# Color_Detector_RPi_Board.net
KiCad netlist of a schematic drawn in EAGLE
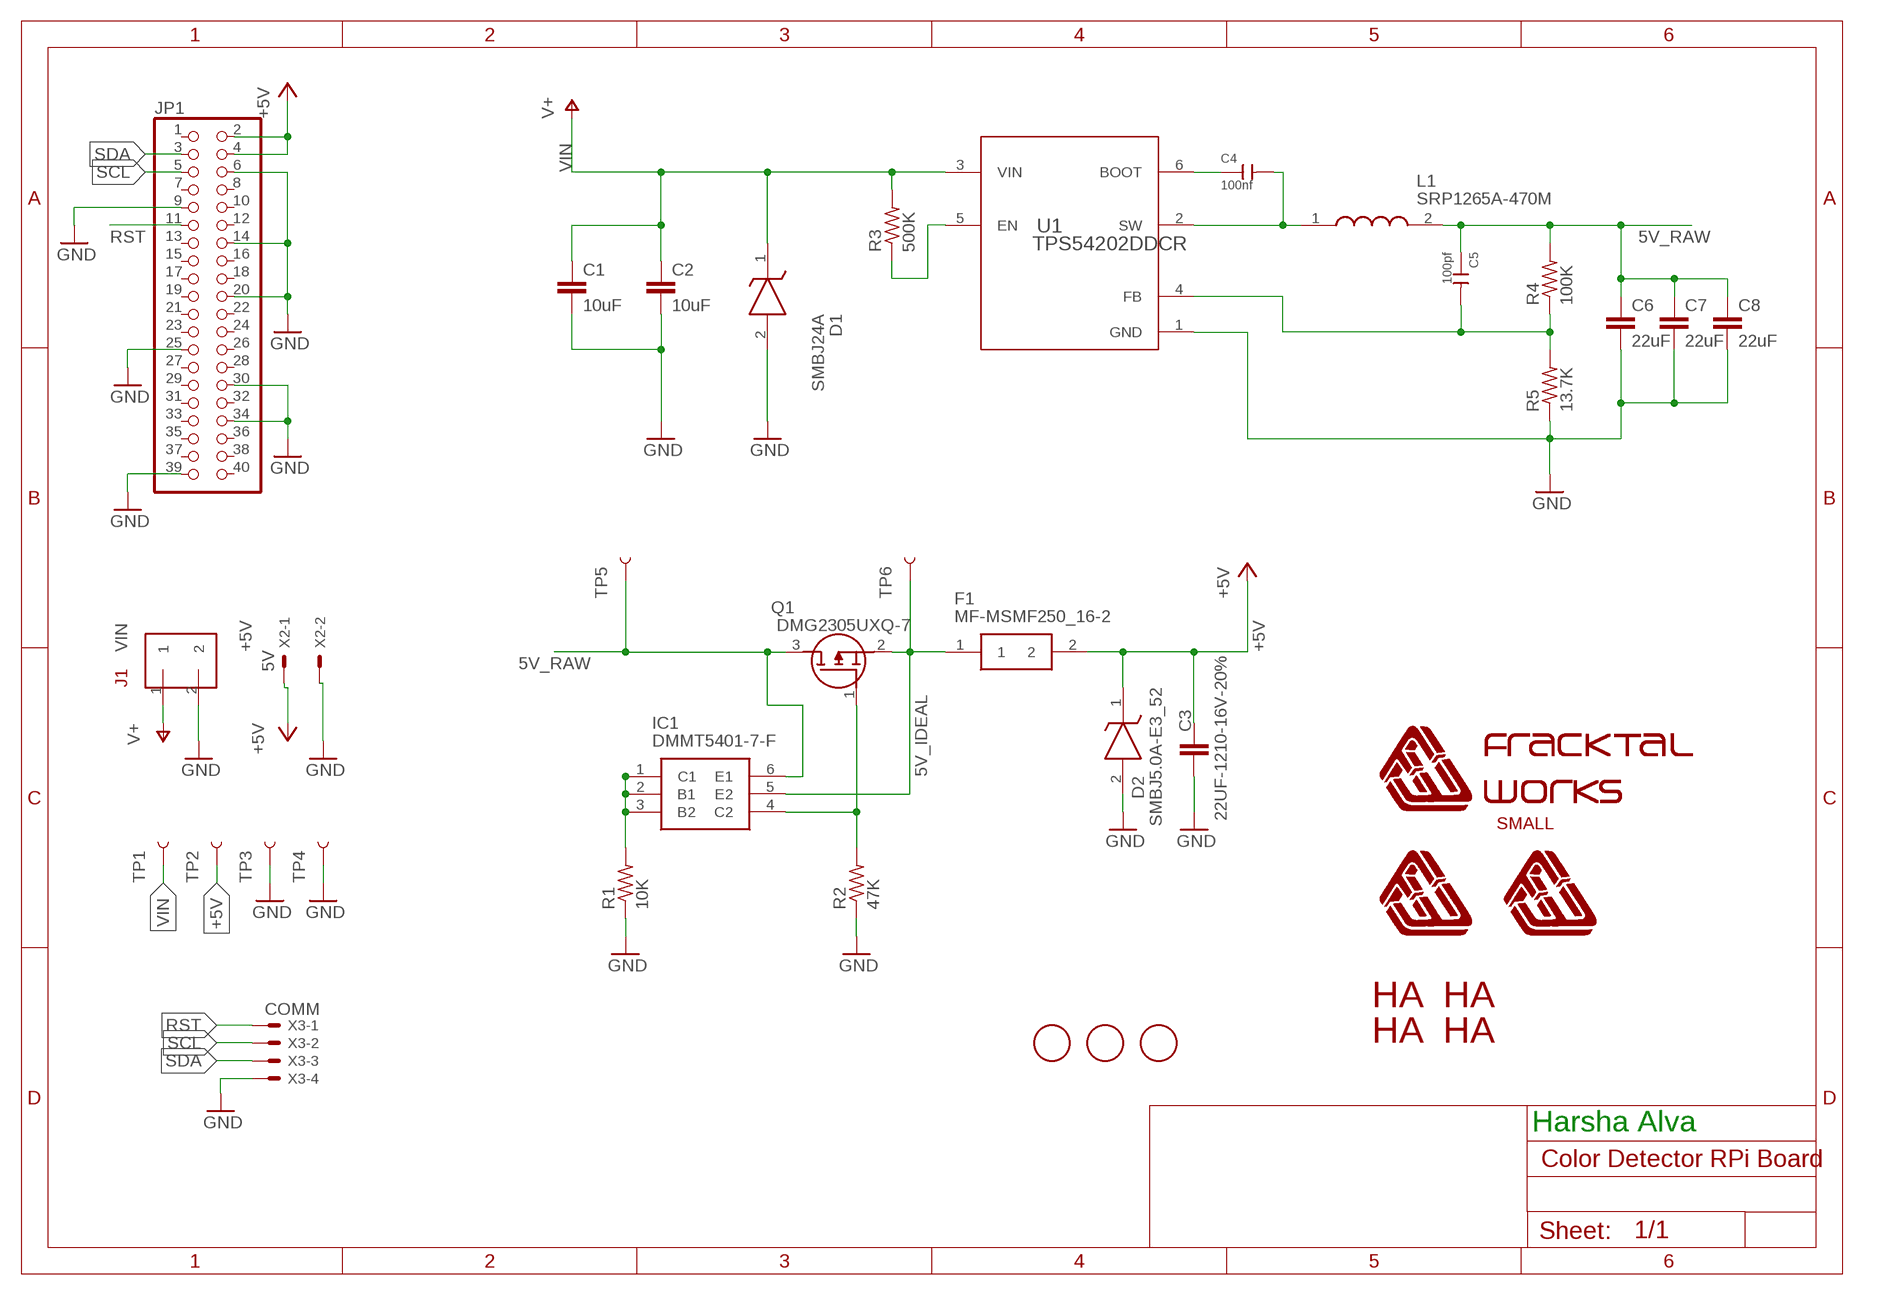
[diagram p0: schematic, sheet 1]

(export (version "E")
  (design (tool "Eeschema 10.0.6"))
  (components
    (comp (ref "$1_39_$_2020-06-29_16-08-13")
      (value "HA_MARK")
      (footprint "eagle-import:HA_MARK")
      (libsource (lib "eagle-import") (part "HA_MARK"))
    )
    (comp (ref "$1_40_$_2020-06-29_16-08-1")
      (value "HA_MARK")
      (footprint "eagle-import:HA_MARK")
      (libsource (lib "eagle-import") (part "HA_MARK"))
    )
    (comp (ref "$1_40_$_2020-06-29_16-08-13")
      (value "HA_MARK")
      (footprint "eagle-import:HA_MARK")
      (libsource (lib "eagle-import") (part "HA_MARK"))
    )
    (comp (ref "C1")
      (value "10uF")
      (footprint "eagle-import:1210")
      (libsource (lib "eagle-import") (part "10UF-1210-50V-20%"))
    )
    (comp (ref "C2")
      (value "10uF")
      (footprint "eagle-import:1210")
      (libsource (lib "eagle-import") (part "10UF-1210-50V-20%"))
    )
    (comp (ref "C3")
      (value "22UF-1210-16V-20%")
      (footprint "eagle-import:1210")
      (libsource (lib "eagle-import") (part "22UF-1210-16V-20%"))
    )
    (comp (ref "C4")
      (value "100nf")
      (footprint "eagle-import:C0603")
      (fields (field (name "MPN") "CC0603KRX7R9BB104"))
      (libsource (lib "eagle-import") (part "CERAMIC-100NF-50V-10%-X7R(0603)"))
    )
    (comp (ref "C5")
      (value "100pf")
      (footprint "eagle-import:C0603")
      (fields (field (name "MPN") "CC0603JRNPO9BN101"))
      (libsource (lib "eagle-import") (part "CERAMIC-100PF-50V-5%-NPO(0603)"))
    )
    (comp (ref "C6")
      (value "22uF")
      (footprint "eagle-import:1210")
      (libsource (lib "eagle-import") (part "22UF-1210-16V-20%"))
    )
    (comp (ref "C7")
      (value "22uF")
      (footprint "eagle-import:1210")
      (libsource (lib "eagle-import") (part "22UF-1210-16V-20%"))
    )
    (comp (ref "C8")
      (value "22uF")
      (footprint "eagle-import:1210")
      (libsource (lib "eagle-import") (part "22UF-1210-16V-20%"))
    )
    (comp (ref "D1")
      (value "SMBJ24A")
      (footprint "eagle-import:DIOM5436X244N")
      (fields (field (name "MOUSER_PART_NUMBER") "652-SMBJ24A"))
      (libsource (lib "eagle-import") (part "SMBJ24A"))
    )
    (comp (ref "D2")
      (value "SMBJ5.0A-E3_52")
      (footprint "eagle-import:DIOM5436X244N")
      (fields
        (field (name "MANUFACTURER_PART_NUMBER") "SMBJ5.0A-E3/52")
        (field (name "MOUSER_PART_NUMBER") "625-SMBJ5.0A-E3")
        (field (name "RS_PART_NUMBER") "1652507")
      )
      (libsource (lib "eagle-import") (part "SMBJ5.0A-E3_52"))
    )
    (comp (ref "F1")
      (value "MF-MSMF250_16-2")
      (footprint "eagle-import:FUSC4632X160N")
      (fields
        (field (name "MANUFACTURER_PART_NUMBER") "MF-MSMF250/16-2")
        (field (name "MOUSER_PART_NUMBER") "652-MF-MSMF250/16-2")
        (field (name "RS_PART_NUMBER") "6478229P")
      )
      (libsource (lib "eagle-import") (part "MF-MSMF250_16-2"))
    )
    (comp (ref "FWLOGO_1")
      (value "FWLOGO")
      (footprint "eagle-import:FWLOGO")
      (libsource (lib "eagle-import") (part "FWLOGO"))
    )
    (comp (ref "FWLOGO_2")
      (value "FWLOGO")
      (footprint "eagle-import:FWLOGO")
      (libsource (lib "eagle-import") (part "FWLOGO"))
    )
    (comp (ref "FW_TXT_S_2")
      (value "FWLOGO_TEXT_SMALL")
      (footprint "eagle-import:FWLOGO_TEXT_SMALL")
      (libsource (lib "eagle-import") (part "FWLOGO_TEXT_SMALL"))
    )
    (comp (ref "IC1")
      (value "DMMT5401-7-F")
      (footprint "eagle-import:SOT95P275X110-6N")
      (fields (field (name "MOUSER_PART_NUMBER") "621-DMMT5401-7-F"))
      (libsource (lib "eagle-import") (part "DMMT5401-7-F"))
    )
    (comp (ref "J1")
      (value "TERMINALBLOCK/TOYO/2PIN/5MMPITCH")
      (footprint "eagle-import:TERMINALBLOCK_TOYO_2PIN_5MMPITCH")
      (libsource (lib "eagle-import") (part "TERMINALBLOCK/TOYO/2PIN/5MMPITCH"))
    )
    (comp (ref "JP1")
      (value "RASPBERRYPI_3B_GPIO")
      (footprint "eagle-import:RASPBERRYPI_3B_GPIO")
      (libsource (lib "eagle-import") (part "RASPBERRYPI_3B_GPIO"))
    )
    (comp (ref "L1")
      (value "SRP1265A-470M")
      (footprint "eagle-import:SRP1265A")
      (fields
        (field (name "MOUSER_PART_NUMBER") "652-SRP1265A-470M")
        (field (name "RS_PART_NUMBER") "8193513P")
      )
      (libsource (lib "eagle-import") (part "SRP1265A-470M"))
    )
    (comp (ref "M_HA_1")
      (value "HA_MARK")
      (footprint "eagle-import:HA_MARK")
      (libsource (lib "eagle-import") (part "HA_MARK"))
    )
    (comp (ref "Q1")
      (value "DMG2305UXQ-7")
      (footprint "eagle-import:SOT96P240X110-3N")
      (fields (field (name "MOUSER_PART_NUMBER") "621-DMG2305UXQ-7"))
      (libsource (lib "eagle-import") (part "DMG2305UXQ-7"))
    )
    (comp (ref "R1")
      (value "10K")
      (footprint "eagle-import:M0805")
      (libsource (lib "eagle-import") (part "resistor_348_R-US_M0805"))
    )
    (comp (ref "R2")
      (value "47K")
      (footprint "eagle-import:M0805")
      (libsource (lib "eagle-import") (part "resistor_348_R-US_M0805"))
    )
    (comp (ref "R3")
      (value "500K")
      (footprint "eagle-import:R0603")
      (libsource (lib "eagle-import") (part "R-US_R0603"))
    )
    (comp (ref "R4")
      (value "100K")
      (footprint "eagle-import:R0603")
      (libsource (lib "eagle-import") (part "R-US_R0603"))
    )
    (comp (ref "R5")
      (value "13.7K")
      (footprint "eagle-import:R0603")
      (libsource (lib "eagle-import") (part "R-US_R0603"))
    )
    (comp (ref "TP1")
      (value "TEST-POINT3X5")
      (footprint "eagle-import:PAD.03X.05")
      (libsource (lib "eagle-import") (part "TEST-POINT3X5"))
    )
    (comp (ref "TP2")
      (value "TEST-POINT3X5")
      (footprint "eagle-import:PAD.03X.05")
      (libsource (lib "eagle-import") (part "TEST-POINT3X5"))
    )
    (comp (ref "TP3")
      (value "TEST-POINT3X5")
      (footprint "eagle-import:PAD.03X.05")
      (libsource (lib "eagle-import") (part "TEST-POINT3X5"))
    )
    (comp (ref "TP4")
      (value "TEST-POINT3X5")
      (footprint "eagle-import:PAD.03X.05")
      (libsource (lib "eagle-import") (part "TEST-POINT3X5"))
    )
    (comp (ref "TP5")
      (value "TEST-POINT3X5")
      (footprint "eagle-import:PAD.03X.05")
      (libsource (lib "eagle-import") (part "TEST-POINT3X5"))
    )
    (comp (ref "TP6")
      (value "TEST-POINT3X5")
      (footprint "eagle-import:PAD.03X.05")
      (libsource (lib "eagle-import") (part "TEST-POINT3X5"))
    )
    (comp (ref "U$1")
      (value "FIDUCIAL")
      (footprint "eagle-import:FIDUCIAL_1MM")
      (libsource (lib "eagle-import") (part "FIDUCIAL"))
    )
    (comp (ref "U$2")
      (value "FIDUCIAL")
      (footprint "eagle-import:FIDUCIAL_1MM")
      (libsource (lib "eagle-import") (part "FIDUCIAL"))
    )
    (comp (ref "U$3")
      (value "FIDUCIAL")
      (footprint "eagle-import:FIDUCIAL_1MM")
      (libsource (lib "eagle-import") (part "FIDUCIAL"))
    )
    (comp (ref "U1")
      (value "TPS54202DDCR")
      (footprint "eagle-import:DDC0006A_N")
      (fields
        (field (name "ALTERNATEPARTNUMBER") "TPS54202DDCT")
        (field (name "MANUFACTURER") "Texas Instruments")
      )
      (libsource (lib "eagle-import") (part "TPS54202DDCR"))
    )
    (comp (ref "X2")
      (value "5V")
      (footprint "eagle-import:JST-XH-02-PACKAGE-LONG-PAD")
      (libsource (lib "eagle-import") (part "JST-XH-02-PIN-LONG-PAD"))
    )
    (comp (ref "X3")
      (value "COMM")
      (footprint "eagle-import:JST-XH-04-PACKAGE-ROUND-PAD")
      (libsource (lib "eagle-import") (part "JST-XH-04-PIN-ROUND-PAD"))
    )
  )
  (nets
    (net (code "1") (name "+5V") (class "Default")
      (node (ref "C3") (pin "2") (pinfunction "2_2") (pintype "passive"))
      (node (ref "D2") (pin "1") (pinfunction "K_1") (pintype "bidirectional"))
      (node (ref "F1") (pin "2") (pinfunction "2_2") (pintype "bidirectional"))
      (node (ref "JP1") (pin "2") (pinfunction "2_2") (pintype "passive"))
      (node (ref "JP1") (pin "4") (pinfunction "4_4") (pintype "passive"))
      (node (ref "TP2") (pin "P$1") (pinfunction "1_P$1") (pintype "bidirectional"))
      (node (ref "X2") (pin "1") (pinfunction "S_1") (pintype "passive"))
    )
    (net (code "2") (name "/5V_IDEAL") (class "Default")
      (node (ref "F1") (pin "1") (pinfunction "1_1") (pintype "bidirectional"))
      (node (ref "IC1") (pin "5") (pinfunction "E2_5") (pintype "bidirectional"))
      (node (ref "Q1") (pin "2") (pinfunction "S_2") (pintype "bidirectional"))
      (node (ref "TP6") (pin "P$1") (pinfunction "1_P$1") (pintype "bidirectional"))
    )
    (net (code "3") (name "/5V_RAW") (class "Default")
      (node (ref "C5") (pin "1") (pinfunction "1_1") (pintype "passive"))
      (node (ref "C6") (pin "1") (pinfunction "1_1") (pintype "passive"))
      (node (ref "C7") (pin "1") (pinfunction "1_1") (pintype "passive"))
      (node (ref "C8") (pin "1") (pinfunction "1_1") (pintype "passive"))
      (node (ref "IC1") (pin "6") (pinfunction "E1_6") (pintype "bidirectional"))
      (node (ref "L1") (pin "2") (pinfunction "2_2") (pintype "bidirectional"))
      (node (ref "Q1") (pin "3") (pinfunction "D_3") (pintype "bidirectional"))
      (node (ref "R4") (pin "2") (pinfunction "2_2") (pintype "passive"))
      (node (ref "TP5") (pin "P$1") (pinfunction "1_P$1") (pintype "bidirectional"))
    )
    (net (code "4") (name "GND") (class "Default")
      (node (ref "C1") (pin "2") (pinfunction "2_2") (pintype "passive"))
      (node (ref "C2") (pin "2") (pinfunction "2_2") (pintype "passive"))
      (node (ref "C3") (pin "1") (pinfunction "1_1") (pintype "passive"))
      (node (ref "C6") (pin "2") (pinfunction "2_2") (pintype "passive"))
      (node (ref "C7") (pin "2") (pinfunction "2_2") (pintype "passive"))
      (node (ref "C8") (pin "2") (pinfunction "2_2") (pintype "passive"))
      (node (ref "D1") (pin "2") (pinfunction "A_2") (pintype "bidirectional"))
      (node (ref "D2") (pin "2") (pinfunction "A_2") (pintype "bidirectional"))
      (node (ref "J1") (pin "2") (pinfunction "2_2") (pintype "bidirectional"))
      (node (ref "JP1") (pin "14") (pinfunction "14_14") (pintype "passive"))
      (node (ref "JP1") (pin "20") (pinfunction "20_20") (pintype "passive"))
      (node (ref "JP1") (pin "25") (pinfunction "25_25") (pintype "passive"))
      (node (ref "JP1") (pin "30") (pinfunction "30_30") (pintype "passive"))
      (node (ref "JP1") (pin "34") (pinfunction "34_34") (pintype "passive"))
      (node (ref "JP1") (pin "39") (pinfunction "39_39") (pintype "passive"))
      (node (ref "JP1") (pin "6") (pinfunction "6_6") (pintype "passive"))
      (node (ref "JP1") (pin "9") (pinfunction "9_9") (pintype "passive"))
      (node (ref "R1") (pin "1") (pinfunction "1_1") (pintype "passive"))
      (node (ref "R2") (pin "1") (pinfunction "1_1") (pintype "passive"))
      (node (ref "R5") (pin "1") (pinfunction "1_1") (pintype "passive"))
      (node (ref "TP3") (pin "P$1") (pinfunction "1_P$1") (pintype "bidirectional"))
      (node (ref "TP4") (pin "P$1") (pinfunction "1_P$1") (pintype "bidirectional"))
      (node (ref "U1") (pin "1") (pinfunction "GND_1") (pintype "power_in"))
      (node (ref "X2") (pin "2") (pinfunction "S_2") (pintype "passive"))
      (node (ref "X3") (pin "4") (pinfunction "S_4") (pintype "passive"))
    )
    (net (code "5") (name "Net-(IC1-B1)") (class "Default")
      (node (ref "IC1") (pin "1") (pinfunction "C1_1") (pintype "bidirectional"))
      (node (ref "IC1") (pin "2") (pinfunction "B1_2") (pintype "bidirectional"))
      (node (ref "IC1") (pin "3") (pinfunction "B2_3") (pintype "bidirectional"))
      (node (ref "R1") (pin "2") (pinfunction "2_2") (pintype "passive"))
    )
    (net (code "6") (name "Net-(IC1-C2)") (class "Default")
      (node (ref "IC1") (pin "4") (pinfunction "C2_4") (pintype "bidirectional"))
      (node (ref "Q1") (pin "1") (pinfunction "G_1") (pintype "bidirectional"))
      (node (ref "R2") (pin "2") (pinfunction "2_2") (pintype "passive"))
    )
    (net (code "7") (name "Net-(U1-BOOT)") (class "Default")
      (node (ref "C4") (pin "1") (pinfunction "1_1") (pintype "passive"))
      (node (ref "U1") (pin "6") (pinfunction "BOOT_6") (pintype "power_in"))
    )
    (net (code "8") (name "Net-(U1-EN)") (class "Default")
      (node (ref "R3") (pin "1") (pinfunction "1_1") (pintype "passive"))
      (node (ref "U1") (pin "5") (pinfunction "EN_5") (pintype "input"))
    )
    (net (code "9") (name "Net-(U1-FB)") (class "Default")
      (node (ref "C5") (pin "2") (pinfunction "2_2") (pintype "passive"))
      (node (ref "R4") (pin "1") (pinfunction "1_1") (pintype "passive"))
      (node (ref "R5") (pin "2") (pinfunction "2_2") (pintype "passive"))
      (node (ref "U1") (pin "4") (pinfunction "FB_4") (pintype "input"))
    )
    (net (code "10") (name "Net-(U1-SW)") (class "Default")
      (node (ref "C4") (pin "2") (pinfunction "2_2") (pintype "passive"))
      (node (ref "L1") (pin "1") (pinfunction "1_1") (pintype "bidirectional"))
      (node (ref "U1") (pin "2") (pinfunction "SW_2") (pintype "power_in"))
    )
    (net (code "11") (name "RST") (class "Default")
      (node (ref "JP1") (pin "11") (pinfunction "11_11") (pintype "passive"))
      (node (ref "X3") (pin "1") (pinfunction "S_1") (pintype "passive"))
    )
    (net (code "12") (name "SCL") (class "Default")
      (node (ref "JP1") (pin "5") (pinfunction "5_5") (pintype "passive"))
      (node (ref "X3") (pin "2") (pinfunction "S_2") (pintype "passive"))
    )
    (net (code "13") (name "SDA") (class "Default")
      (node (ref "JP1") (pin "3") (pinfunction "3_3") (pintype "passive"))
      (node (ref "X3") (pin "3") (pinfunction "S_3") (pintype "passive"))
    )
    (net (code "14") (name "VIN") (class "Default")
      (node (ref "C1") (pin "1") (pinfunction "1_1") (pintype "passive"))
      (node (ref "C2") (pin "1") (pinfunction "1_1") (pintype "passive"))
      (node (ref "D1") (pin "1") (pinfunction "K_1") (pintype "bidirectional"))
      (node (ref "J1") (pin "1") (pinfunction "1_1") (pintype "bidirectional"))
      (node (ref "R3") (pin "2") (pinfunction "2_2") (pintype "passive"))
      (node (ref "TP1") (pin "P$1") (pinfunction "1_P$1") (pintype "bidirectional"))
      (node (ref "U1") (pin "3") (pinfunction "VIN_3") (pintype "power_in"))
    )
    (net (code "15") (name "unconnected-(JP1-Pad1)") (class "Default")
      (node (ref "JP1") (pin "1") (pinfunction "1_1") (pintype "passive"))
    )
    (net (code "16") (name "unconnected-(JP1-Pad7)") (class "Default")
      (node (ref "JP1") (pin "7") (pinfunction "7_7") (pintype "passive"))
    )
    (net (code "17") (name "unconnected-(JP1-Pad8)") (class "Default")
      (node (ref "JP1") (pin "8") (pinfunction "8_8") (pintype "passive"))
    )
    (net (code "18") (name "unconnected-(JP1-Pad10)") (class "Default")
      (node (ref "JP1") (pin "10") (pinfunction "10_10") (pintype "passive"))
    )
    (net (code "19") (name "unconnected-(JP1-Pad12)") (class "Default")
      (node (ref "JP1") (pin "12") (pinfunction "12_12") (pintype "passive"))
    )
    (net (code "20") (name "unconnected-(JP1-Pad13)") (class "Default")
      (node (ref "JP1") (pin "13") (pinfunction "13_13") (pintype "passive"))
    )
    (net (code "21") (name "unconnected-(JP1-Pad15)") (class "Default")
      (node (ref "JP1") (pin "15") (pinfunction "15_15") (pintype "passive"))
    )
    (net (code "22") (name "unconnected-(JP1-Pad16)") (class "Default")
      (node (ref "JP1") (pin "16") (pinfunction "16_16") (pintype "passive"))
    )
    (net (code "23") (name "unconnected-(JP1-Pad17)") (class "Default")
      (node (ref "JP1") (pin "17") (pinfunction "17_17") (pintype "passive"))
    )
    (net (code "24") (name "unconnected-(JP1-Pad18)") (class "Default")
      (node (ref "JP1") (pin "18") (pinfunction "18_18") (pintype "passive"))
    )
    (net (code "25") (name "unconnected-(JP1-Pad19)") (class "Default")
      (node (ref "JP1") (pin "19") (pinfunction "19_19") (pintype "passive"))
    )
    (net (code "26") (name "unconnected-(JP1-Pad21)") (class "Default")
      (node (ref "JP1") (pin "21") (pinfunction "21_21") (pintype "passive"))
    )
    (net (code "27") (name "unconnected-(JP1-Pad22)") (class "Default")
      (node (ref "JP1") (pin "22") (pinfunction "22_22") (pintype "passive"))
    )
    (net (code "28") (name "unconnected-(JP1-Pad23)") (class "Default")
      (node (ref "JP1") (pin "23") (pinfunction "23_23") (pintype "passive"))
    )
    (net (code "29") (name "unconnected-(JP1-Pad24)") (class "Default")
      (node (ref "JP1") (pin "24") (pinfunction "24_24") (pintype "passive"))
    )
    (net (code "30") (name "unconnected-(JP1-Pad26)") (class "Default")
      (node (ref "JP1") (pin "26") (pinfunction "26_26") (pintype "passive"))
    )
    (net (code "31") (name "unconnected-(JP1-Pad27)") (class "Default")
      (node (ref "JP1") (pin "27") (pinfunction "27_27") (pintype "passive"))
    )
    (net (code "32") (name "unconnected-(JP1-Pad28)") (class "Default")
      (node (ref "JP1") (pin "28") (pinfunction "28_28") (pintype "passive"))
    )
    (net (code "33") (name "unconnected-(JP1-Pad29)") (class "Default")
      (node (ref "JP1") (pin "29") (pinfunction "29_29") (pintype "passive"))
    )
    (net (code "34") (name "unconnected-(JP1-Pad31)") (class "Default")
      (node (ref "JP1") (pin "31") (pinfunction "31_31") (pintype "passive"))
    )
    (net (code "35") (name "unconnected-(JP1-Pad32)") (class "Default")
      (node (ref "JP1") (pin "32") (pinfunction "32_32") (pintype "passive"))
    )
    (net (code "36") (name "unconnected-(JP1-Pad33)") (class "Default")
      (node (ref "JP1") (pin "33") (pinfunction "33_33") (pintype "passive"))
    )
    (net (code "37") (name "unconnected-(JP1-Pad35)") (class "Default")
      (node (ref "JP1") (pin "35") (pinfunction "35_35") (pintype "passive"))
    )
    (net (code "38") (name "unconnected-(JP1-Pad36)") (class "Default")
      (node (ref "JP1") (pin "36") (pinfunction "36_36") (pintype "passive"))
    )
    (net (code "39") (name "unconnected-(JP1-Pad37)") (class "Default")
      (node (ref "JP1") (pin "37") (pinfunction "37_37") (pintype "passive"))
    )
    (net (code "40") (name "unconnected-(JP1-Pad38)") (class "Default")
      (node (ref "JP1") (pin "38") (pinfunction "38_38") (pintype "passive"))
    )
    (net (code "41") (name "unconnected-(JP1-Pad40)") (class "Default")
      (node (ref "JP1") (pin "40") (pinfunction "40_40") (pintype "passive"))
    )
  )
)
